# neo_retro_speedo_v1.net
KiCad netlist of a schematic drawn in EAGLE
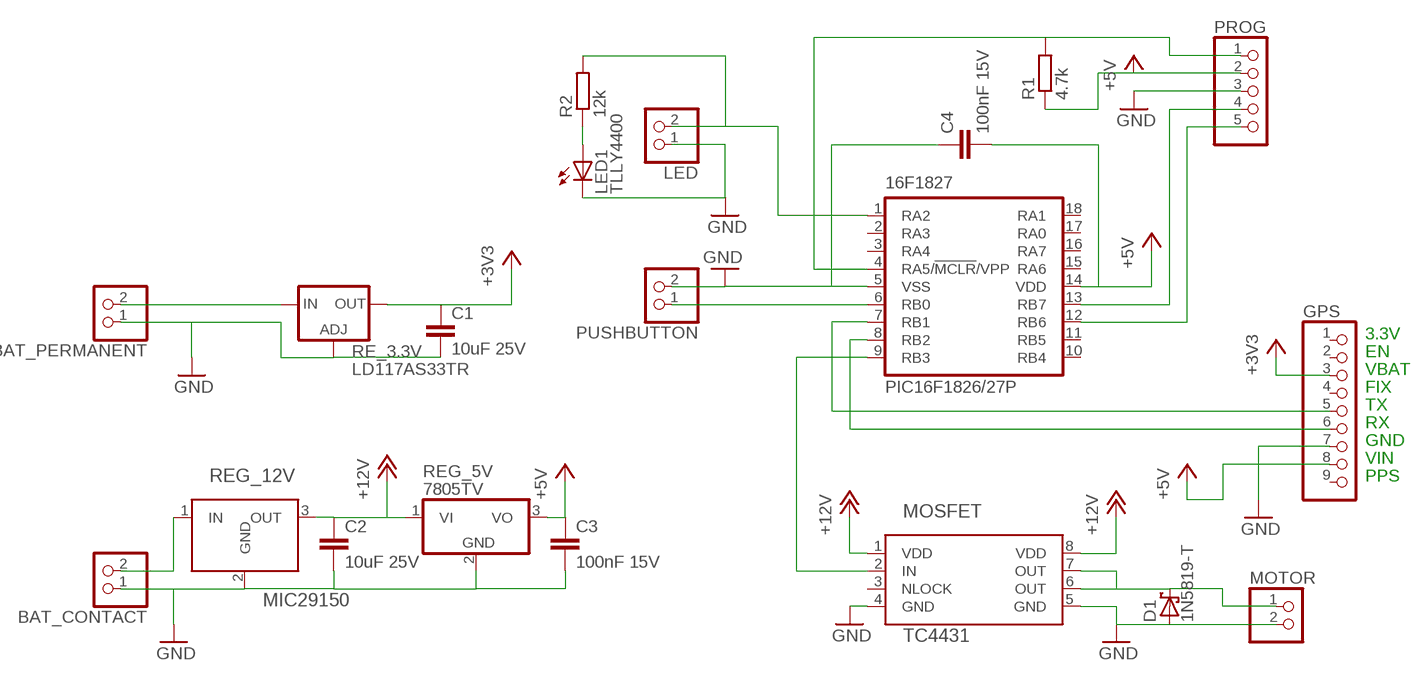
[diagram p0: schematic, sheet 1]

(export (version "E")
  (design (tool "Eeschema 10.0.6"))
  (components
    (comp (ref "16F1827")
      (value "PIC16F1826/27P")
      (footprint "eagle-import:DIL18")
      (libsource (lib "eagle-import") (part "PIC16F1826/27P"))
    )
    (comp (ref "BAT_CONTACT")
      (value "PINHD-1X2")
      (footprint "eagle-import:1X02")
      (libsource (lib "eagle-import") (part "PINHD-1X2"))
    )
    (comp (ref "BAT_PERMANENT")
      (value "PINHD-1X2")
      (footprint "eagle-import:1X02")
      (libsource (lib "eagle-import") (part "PINHD-1X2"))
    )
    (comp (ref "C1")
      (value "10uF 25V")
      (footprint "eagle-import:C025-030X050")
      (libsource (lib "eagle-import") (part "C-EU025-030X050"))
    )
    (comp (ref "C2")
      (value "10uF 25V")
      (footprint "eagle-import:C025-030X050")
      (libsource (lib "eagle-import") (part "C-EU025-030X050"))
    )
    (comp (ref "C3")
      (value "100nF 15V")
      (footprint "eagle-import:C025-030X050")
      (libsource (lib "eagle-import") (part "C-EU025-030X050"))
    )
    (comp (ref "C4")
      (value "100nF 15V")
      (footprint "eagle-import:C025-030X050")
      (libsource (lib "eagle-import") (part "C-EU025-030X050"))
    )
    (comp (ref "D1")
      (value "1N5819-T")
      (footprint "eagle-import:DO41-7.6")
      (libsource (lib "eagle-import") (part "1N5819-T"))
    )
    (comp (ref "GPS")
      (value "PINHD-1X9")
      (footprint "eagle-import:1X09")
      (libsource (lib "eagle-import") (part "PINHD-1X9"))
    )
    (comp (ref "LED")
      (value "PINHD-1X2")
      (footprint "eagle-import:1X02")
      (libsource (lib "eagle-import") (part "PINHD-1X2"))
    )
    (comp (ref "LED1")
      (value "TLLY4400")
      (footprint "eagle-import:LED3MM")
      (fields (field (name "MF") "VISHAY SEMICONDUCTOR"))
      (libsource (lib "eagle-import") (part "TLLY4400"))
    )
    (comp (ref "MOSFET")
      (value "TC4431")
      (footprint "eagle-import:DIL08")
      (libsource (lib "eagle-import") (part "TC4431"))
    )
    (comp (ref "MOTOR")
      (value "PINHD-1X2")
      (footprint "eagle-import:1X02")
      (libsource (lib "eagle-import") (part "PINHD-1X2"))
    )
    (comp (ref "PROG")
      (value "PINHD-1X5")
      (footprint "eagle-import:1X05")
      (libsource (lib "eagle-import") (part "PINHD-1X5"))
    )
    (comp (ref "PUSHBUTTON")
      (value "PINHD-1X2")
      (footprint "eagle-import:1X02")
      (libsource (lib "eagle-import") (part "PINHD-1X2"))
    )
    (comp (ref "R1")
      (value "4.7k")
      (footprint "eagle-import:0204_7")
      (libsource (lib "eagle-import") (part "R-EU_0204/7"))
    )
    (comp (ref "R2")
      (value "12k")
      (footprint "eagle-import:0204_7")
      (libsource (lib "eagle-import") (part "R-EU_0204/7"))
    )
    (comp (ref "REG_5V")
      (value "7805TV")
      (footprint "eagle-import:TO220V")
      (libsource (lib "eagle-import") (part "78TV05"))
    )
    (comp (ref "REG_12V")
      (value "MIC29150")
      (footprint "eagle-import:TO220S")
      (libsource (lib "eagle-import") (part "MIC29150"))
    )
    (comp (ref "RE_3.3V")
      (value "LD117AS33TR")
      (footprint "eagle-import:SOT223")
      (libsource (lib "eagle-import") (part "LD117A?S33TR"))
    )
  )
  (nets
    (net (code "1") (name "+3V3") (class "Default")
      (node (ref "C1") (pin "1") (pinfunction "1_1") (pintype "passive"))
      (node (ref "GPS") (pin "3") (pinfunction "3_3") (pintype "passive"))
      (node (ref "RE_3.3V") (pin "4") (pinfunction "OUT_4") (pintype "passive"))
    )
    (net (code "2") (name "+5V") (class "Default")
      (node (ref "16F1827") (pin "14") (pinfunction "VDD_14") (pintype "power_in"))
      (node (ref "C3") (pin "1") (pinfunction "1_1") (pintype "passive"))
      (node (ref "C4") (pin "2") (pinfunction "2_2") (pintype "passive"))
      (node (ref "GPS") (pin "8") (pinfunction "8_8") (pintype "passive"))
      (node (ref "PROG") (pin "2") (pinfunction "2_2") (pintype "passive"))
      (node (ref "R1") (pin "1") (pinfunction "1_1") (pintype "passive"))
      (node (ref "REG_5V") (pin "3") (pinfunction "VO_3") (pintype "passive"))
    )
    (net (code "3") (name "+12V") (class "Default")
      (node (ref "C2") (pin "1") (pinfunction "1_1") (pintype "passive"))
      (node (ref "MOSFET") (pin "1") (pinfunction "VDD_1") (pintype "power_in"))
      (node (ref "MOSFET") (pin "8") (pinfunction "VDD_8") (pintype "power_in"))
      (node (ref "REG_12V") (pin "3") (pinfunction "OUT_3") (pintype "output"))
      (node (ref "REG_5V") (pin "1") (pinfunction "VI_1") (pintype "input"))
    )
    (net (code "4") (name "GND") (class "Default")
      (node (ref "16F1827") (pin "5") (pinfunction "VSS_5") (pintype "power_in"))
      (node (ref "BAT_CONTACT") (pin "1") (pinfunction "1_1") (pintype "passive"))
      (node (ref "BAT_PERMANENT") (pin "1") (pinfunction "1_1") (pintype "passive"))
      (node (ref "C1") (pin "2") (pinfunction "2_2") (pintype "passive"))
      (node (ref "C2") (pin "2") (pinfunction "2_2") (pintype "passive"))
      (node (ref "C3") (pin "2") (pinfunction "2_2") (pintype "passive"))
      (node (ref "C4") (pin "1") (pinfunction "1_1") (pintype "passive"))
      (node (ref "D1") (pin "A") (pinfunction "A_A") (pintype "passive"))
      (node (ref "GPS") (pin "7") (pinfunction "7_7") (pintype "passive"))
      (node (ref "LED") (pin "1") (pinfunction "1_1") (pintype "passive"))
      (node (ref "LED1") (pin "K") (pinfunction "C_K") (pintype "passive"))
      (node (ref "MOSFET") (pin "4") (pinfunction "GND_4") (pintype "power_in"))
      (node (ref "MOSFET") (pin "5") (pinfunction "GND_5") (pintype "power_in"))
      (node (ref "MOTOR") (pin "2") (pinfunction "2_2") (pintype "passive"))
      (node (ref "PROG") (pin "3") (pinfunction "3_3") (pintype "passive"))
      (node (ref "PUSHBUTTON") (pin "2") (pinfunction "2_2") (pintype "passive"))
      (node (ref "REG_12V") (pin "2") (pinfunction "GND_2") (pintype "power_in"))
      (node (ref "REG_5V") (pin "2") (pinfunction "GND_2") (pintype "passive"))
      (node (ref "RE_3.3V") (pin "1") (pinfunction "ADJ_1") (pintype "input"))
    )
    (net (code "5") (name "Net-(16F1827-RA2)") (class "Default")
      (node (ref "16F1827") (pin "1") (pinfunction "RA2_1") (pintype "bidirectional"))
      (node (ref "LED") (pin "2") (pinfunction "2_2") (pintype "passive"))
      (node (ref "R2") (pin "2") (pinfunction "2_2") (pintype "passive"))
    )
    (net (code "6") (name "Net-(16F1827-RA5{slash}~{MCLR}{slash}VPP)") (class "Default")
      (node (ref "16F1827") (pin "4") (pinfunction "RA5/~{MCLR}/VPP_4") (pintype "bidirectional"))
      (node (ref "PROG") (pin "1") (pinfunction "1_1") (pintype "passive"))
      (node (ref "R1") (pin "2") (pinfunction "2_2") (pintype "passive"))
    )
    (net (code "7") (name "Net-(16F1827-RB0)") (class "Default")
      (node (ref "16F1827") (pin "6") (pinfunction "RB0_6") (pintype "bidirectional"))
      (node (ref "PUSHBUTTON") (pin "1") (pinfunction "1_1") (pintype "passive"))
    )
    (net (code "8") (name "Net-(16F1827-RB1)") (class "Default")
      (node (ref "16F1827") (pin "7") (pinfunction "RB1_7") (pintype "bidirectional"))
      (node (ref "GPS") (pin "5") (pinfunction "5_5") (pintype "passive"))
    )
    (net (code "9") (name "Net-(16F1827-RB2)") (class "Default")
      (node (ref "16F1827") (pin "8") (pinfunction "RB2_8") (pintype "bidirectional"))
      (node (ref "GPS") (pin "6") (pinfunction "6_6") (pintype "passive"))
    )
    (net (code "10") (name "Net-(16F1827-RB3)") (class "Default")
      (node (ref "16F1827") (pin "9") (pinfunction "RB3_9") (pintype "bidirectional"))
      (node (ref "MOSFET") (pin "2") (pinfunction "IN_2") (pintype "input"))
    )
    (net (code "11") (name "Net-(16F1827-RB6)") (class "Default")
      (node (ref "16F1827") (pin "12") (pinfunction "RB6_12") (pintype "bidirectional"))
      (node (ref "PROG") (pin "5") (pinfunction "5_5") (pintype "passive"))
    )
    (net (code "12") (name "Net-(16F1827-RB7)") (class "Default")
      (node (ref "16F1827") (pin "13") (pinfunction "RB7_13") (pintype "bidirectional"))
      (node (ref "PROG") (pin "4") (pinfunction "4_4") (pintype "passive"))
    )
    (net (code "13") (name "Net-(D1-PadC)") (class "Default")
      (node (ref "D1") (pin "C") (pinfunction "C_C") (pintype "passive"))
      (node (ref "MOSFET") (pin "6") (pinfunction "OUT_6") (pintype "output"))
      (node (ref "MOSFET") (pin "7") (pinfunction "OUT_7") (pintype "output"))
      (node (ref "MOTOR") (pin "1") (pinfunction "1_1") (pintype "passive"))
    )
    (net (code "14") (name "Net-(LED1-PadA)") (class "Default")
      (node (ref "LED1") (pin "A") (pinfunction "A_A") (pintype "passive"))
      (node (ref "R2") (pin "1") (pinfunction "1_1") (pintype "passive"))
    )
    (net (code "15") (name "Net-(REG_12V-IN)") (class "Default")
      (node (ref "BAT_CONTACT") (pin "2") (pinfunction "2_2") (pintype "passive"))
      (node (ref "REG_12V") (pin "1") (pinfunction "IN_1") (pintype "input"))
    )
    (net (code "16") (name "Net-(RE_3.3V-IN)") (class "Default")
      (node (ref "BAT_PERMANENT") (pin "2") (pinfunction "2_2") (pintype "passive"))
      (node (ref "RE_3.3V") (pin "3") (pinfunction "IN_3") (pintype "input"))
    )
    (net (code "17") (name "unconnected-(16F1827-RA0-Pad17)") (class "Default")
      (node (ref "16F1827") (pin "17") (pinfunction "RA0_17") (pintype "bidirectional"))
    )
    (net (code "18") (name "unconnected-(16F1827-RA1-Pad18)") (class "Default")
      (node (ref "16F1827") (pin "18") (pinfunction "RA1_18") (pintype "bidirectional"))
    )
    (net (code "19") (name "unconnected-(16F1827-RA3-Pad2)") (class "Default")
      (node (ref "16F1827") (pin "2") (pinfunction "RA3_2") (pintype "bidirectional"))
    )
    (net (code "20") (name "unconnected-(16F1827-RA4-Pad3)") (class "Default")
      (node (ref "16F1827") (pin "3") (pinfunction "RA4_3") (pintype "bidirectional"))
    )
    (net (code "21") (name "unconnected-(16F1827-RA6-Pad15)") (class "Default")
      (node (ref "16F1827") (pin "15") (pinfunction "RA6_15") (pintype "bidirectional"))
    )
    (net (code "22") (name "unconnected-(16F1827-RA7-Pad16)") (class "Default")
      (node (ref "16F1827") (pin "16") (pinfunction "RA7_16") (pintype "bidirectional"))
    )
    (net (code "23") (name "unconnected-(16F1827-RB4-Pad10)") (class "Default")
      (node (ref "16F1827") (pin "10") (pinfunction "RB4_10") (pintype "bidirectional"))
    )
    (net (code "24") (name "unconnected-(16F1827-RB5-Pad11)") (class "Default")
      (node (ref "16F1827") (pin "11") (pinfunction "RB5_11") (pintype "bidirectional"))
    )
    (net (code "25") (name "unconnected-(GPS-Pad1)") (class "Default")
      (node (ref "GPS") (pin "1") (pinfunction "1_1") (pintype "passive"))
    )
    (net (code "26") (name "unconnected-(GPS-Pad2)") (class "Default")
      (node (ref "GPS") (pin "2") (pinfunction "2_2") (pintype "passive"))
    )
    (net (code "27") (name "unconnected-(GPS-Pad4)") (class "Default")
      (node (ref "GPS") (pin "4") (pinfunction "4_4") (pintype "passive"))
    )
    (net (code "28") (name "unconnected-(GPS-Pad9)") (class "Default")
      (node (ref "GPS") (pin "9") (pinfunction "9_9") (pintype "passive"))
    )
    (net (code "29") (name "unconnected-(MOSFET-NLOCK-Pad3)") (class "Default")
      (node (ref "MOSFET") (pin "3") (pinfunction "NLOCK_3") (pintype "input"))
    )
  )
)
